# MCU.net
KiCad netlist of a schematic drawn in Altium Designer
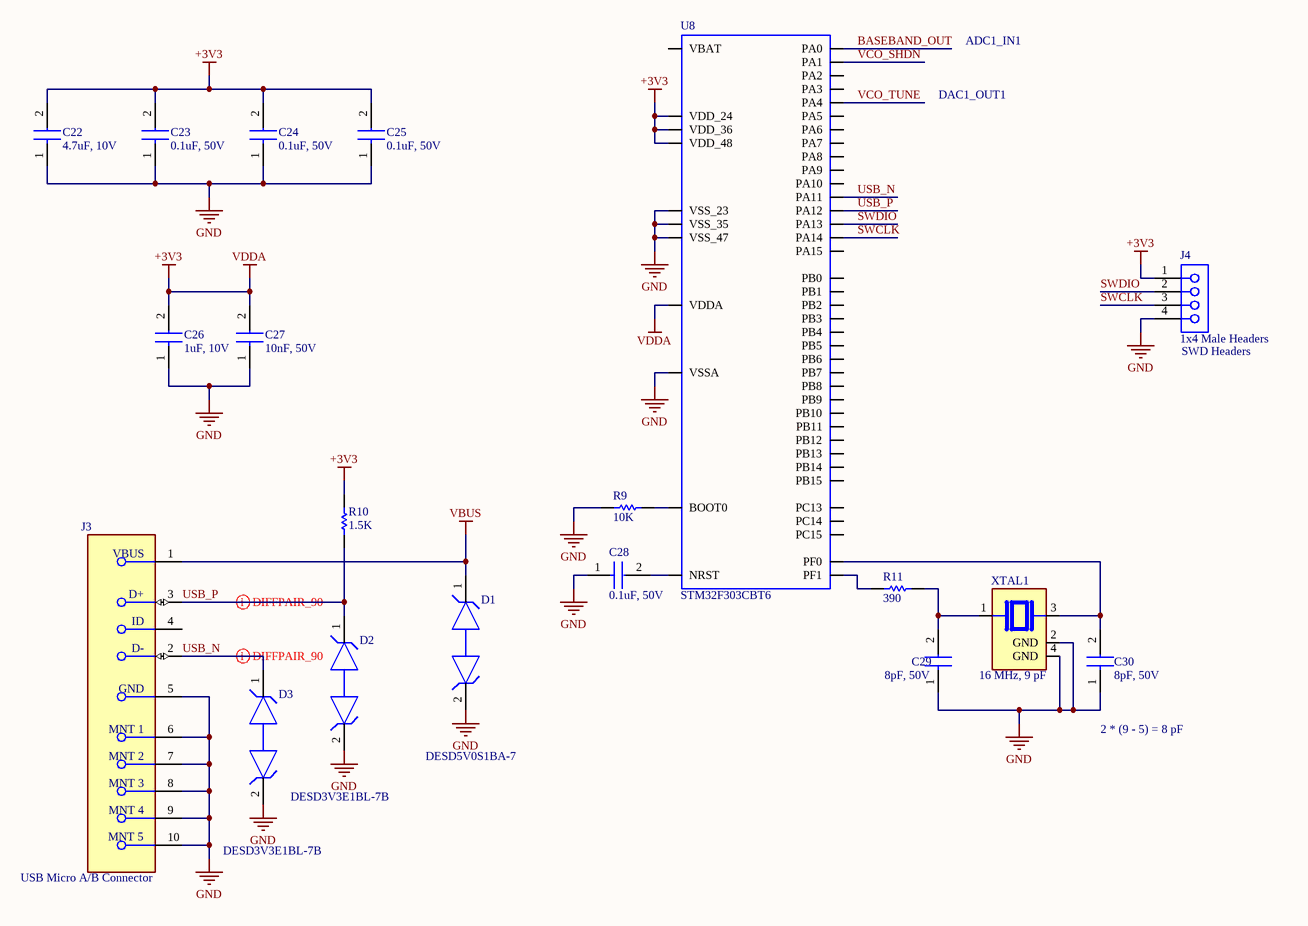
[diagram p0: MCU.SchDoc]

(export (version "E")
  (design (tool "Eeschema 10.0.6"))
  (components
    (comp (ref "C22")
      (value "4.7uF, 10V")
      (footprint "CAPC1608X90N")
      (fields
        (field (name "MANUFACTURER") "Samsung")
        (field (name "MANUFACTURER PART NUMBER") "CL10A475KP8NNNC")
      )
      (libsource (lib "FMCW-Radar-v1") (part "CL10A475KP8NNNC"))
    )
    (comp (ref "C23")
      (value "0.1uF, 50V")
      (footprint "CAP_CC0603_YAG-M")
      (fields
        (field (name "MANUFACTURER") "Yageo")
        (field (name "MANUFACTURER PART NUMBER") "CC0603JRX7R9BB104")
      )
      (libsource (lib "FMCW-Radar-v1") (part "CC0603JRX7R9BB104"))
    )
    (comp (ref "C24")
      (value "0.1uF, 50V")
      (footprint "CAP_CC0603_YAG-M")
      (fields
        (field (name "MANUFACTURER") "Yageo")
        (field (name "MANUFACTURER PART NUMBER") "CC0603JRX7R9BB104")
      )
      (libsource (lib "FMCW-Radar-v1") (part "CC0603JRX7R9BB104"))
    )
    (comp (ref "C25")
      (value "0.1uF, 50V")
      (footprint "CAP_CC0603_YAG-M")
      (fields
        (field (name "MANUFACTURER") "Yageo")
        (field (name "MANUFACTURER PART NUMBER") "CC0603JRX7R9BB104")
      )
      (libsource (lib "FMCW-Radar-v1") (part "CC0603JRX7R9BB104"))
    )
    (comp (ref "C26")
      (value "1uF, 10V")
      (footprint "FP-CL10-IPC_A")
      (fields
        (field (name "MANUFACTURER") "Samsung")
        (field (name "MANUFACTURER PART NUMBER") "CL10B105KP8NNNC")
      )
      (libsource (lib "FMCW-Radar-v1") (part "CL10B105KP8NNNC"))
    )
    (comp (ref "C27")
      (value "10nF, 50V")
      (footprint "CAPC10555_55N_KEM")
      (fields
        (field (name "MANUFACTURER") "KEMET")
        (field (name "MANUFACTURER PART NUMBER") "C0402C103K5RACTU")
      )
      (libsource (lib "FMCW-Radar-v1") (part "C0402C103K5RACTU"))
    )
    (comp (ref "C28")
      (value "0.1uF, 50V")
      (footprint "CAP_CC0603_YAG-M")
      (fields
        (field (name "MANUFACTURER") "Yageo")
        (field (name "MANUFACTURER PART NUMBER") "CC0603JRX7R9BB104")
      )
      (libsource (lib "FMCW-Radar-v1") (part "CC0603JRX7R9BB104"))
    )
    (comp (ref "C29")
      (value "8pF, 50V")
      (footprint "CAPC1005X55N")
      (fields
        (field (name "MANUFACTURER") "Murata")
        (field (name "MANUFACTURER PART NUMBER") "GJM1555C1H8R0BB01D")
      )
      (libsource (lib "FMCW-Radar-v1") (part "GJM1555C1H8R0BB01D"))
    )
    (comp (ref "C30")
      (value "8pF, 50V")
      (footprint "CAPC1005X55N")
      (fields
        (field (name "MANUFACTURER") "Murata")
        (field (name "MANUFACTURER PART NUMBER") "GJM1555C1H8R0BB01D")
      )
      (libsource (lib "FMCW-Radar-v1") (part "GJM1555C1H8R0BB01D"))
    )
    (comp (ref "D1")
      (value "DESD5V0S1BA-7")
      (footprint "FP-SOD323-IPC_C")
      (description "Trans Voltage Suppressor Diode, 130W, 5V V(RWM), Bidirectional, 2 Element, Silicon")
      (fields (field (name "MANUFACTURER") "Diodes Zetex"))
      (libsource (lib "FMCW-Radar-v1") (part "DESD5V0S1BA-7"))
    )
    (comp (ref "D2")
      (value "DESD3V3E1BL-7B")
      (footprint "CR_X1-DFN1006-2_DIO")
      (description "Trans Voltage Suppressor Diode, 35W, 3.3V V(RWM), Bidirectional, 1 Element, Silicon")
      (fields (field (name "MANUFACTURER") "Diodes"))
      (libsource (lib "FMCW-Radar-v1") (part "DESD3V3E1BL-7B"))
    )
    (comp (ref "D3")
      (value "DESD3V3E1BL-7B")
      (footprint "CR_X1-DFN1006-2_DIO")
      (description "Trans Voltage Suppressor Diode, 35W, 3.3V V(RWM), Bidirectional, 1 Element, Silicon")
      (fields (field (name "MANUFACTURER") "Diodes"))
      (libsource (lib "FMCW-Radar-v1") (part "DESD3V3E1BL-7B"))
    )
    (comp (ref "J3")
      (value "USB Micro A/B Connector")
      (footprint "FP-47590-0001-MFG")
      (description "USB Connector, 5 Contact(s), Female, Right Angle, Surface Mount Terminal, Locking, Receptacle")
      (fields (field (name "MANUFACTURER") "Molex") (field (name "MANUFACTURER PART NUMBER") "47590-0001"))
      (libsource (lib "FMCW-Radar-v1") (part "47590-0001"))
    )
    (comp (ref "J4")
      (value "1x4 Male Headers")
      (footprint "61300411121")
      (fields
        (field (name "MANUFACTURER") "Wurth Electronics")
        (field (name "MANUFACTURER PART NUMBER") "61300411121")
      )
      (libsource (lib "FMCW-Radar-v1") (part "61300411121"))
    )
    (comp (ref "R9")
      (value "10K")
      (footprint "RESC1005X37N")
      (fields
        (field (name "MANUFACTURER") "Yageo")
        (field (name "MANUFACTURER PART NUMBER") "AC0402FR-0710KL")
        (field (name "TOLERANCE") "1%")
      )
      (libsource (lib "FMCW-Radar-v1") (part "AC0402FR-0710KL"))
    )
    (comp (ref "R10")
      (value "1.5K")
      (footprint "RESC1005X40N")
      (fields
        (field (name "MANUFACTURER") "Yageo")
        (field (name "MANUFACTURER PART NUMBER") "RC0402FR-071K5L")
        (field (name "TOLERANCE") "1%")
      )
      (libsource (lib "FMCW-Radar-v1") (part "RC0402FR-071K5L"))
    )
    (comp (ref "R11")
      (value "390")
      (footprint "RESC1005X40N")
      (fields
        (field (name "MANUFACTURER") "Yageo")
        (field (name "MANUFACTURER PART NUMBER") "RC0402JR-07390RL")
        (field (name "TOLERANCE") "5%")
      )
      (libsource (lib "FMCW-Radar-v1") (part "RC0402JR-07390RL"))
    )
    (comp (ref "U8")
      (value "STM32F303CBT6")
      (footprint "LQFP-48")
      (description "RISC Microcontroller, 32-Bit, FLASH, CORTEX-M4F CPU, 72MHz, CMOS, PQFP48")
      (fields (field (name "MANUFACTURER") "STMicroelectronics"))
      (libsource (lib "FMCW-Radar-v1") (part "STM32F303CBT6"))
    )
    (comp (ref "XTAL1")
      (value "16 MHz, 9 pF")
      (footprint "XTAL_TSX-3225_16.0000MF18X-AC0")
      (description "Parallel - Fundamental Quartz Crystal, 16MHz Nom")
      (fields
        (field (name "MANUFACTURER") "Epson")
        (field (name "MANUFACTURER PART NUMBER") "TSX-3225 16.0000MF18X-AC0")
      )
      (libsource (lib "FMCW-Radar-v1") (part "TSX-3225 16.0000MF18X-AC0"))
    )
  )
  (nets
    (net (code "1") (name "+3V3") (class "Default")
      (node (ref "C22") (pin "2") (pinfunction "2_2") (pintype "passive"))
      (node (ref "C23") (pin "2") (pinfunction "2_2") (pintype "passive"))
      (node (ref "C24") (pin "2") (pinfunction "2_2") (pintype "passive"))
      (node (ref "C25") (pin "2") (pinfunction "2_2") (pintype "passive"))
      (node (ref "C26") (pin "2") (pinfunction "2_2") (pintype "passive"))
      (node (ref "C27") (pin "2") (pinfunction "2_2") (pintype "passive"))
      (node (ref "J4") (pin "1") (pinfunction "1_1") (pintype "passive"))
      (node (ref "R10") (pin "1") (pinfunction "1_1") (pintype "passive"))
      (node (ref "U8") (pin "24") (pinfunction "VDD_24_24") (pintype "bidirectional"))
      (node (ref "U8") (pin "36") (pinfunction "VDD_36_36") (pintype "bidirectional"))
      (node (ref "U8") (pin "48") (pinfunction "VDD_48_48") (pintype "bidirectional"))
      (node (ref "U8") (pin "9") (pinfunction "VDDA_9") (pintype "bidirectional"))
    )
    (net (code "2") (name "/BASEBAND_OUT") (class "Default")
      (node (ref "U8") (pin "10") (pinfunction "PA0_10") (pintype "bidirectional"))
    )
    (net (code "3") (name "/SWCLK") (class "Default")
      (node (ref "J4") (pin "3") (pinfunction "3_3") (pintype "passive"))
      (node (ref "U8") (pin "37") (pinfunction "PA14_37") (pintype "bidirectional"))
    )
    (net (code "4") (name "/SWDIO") (class "Default")
      (node (ref "J4") (pin "2") (pinfunction "2_2") (pintype "passive"))
      (node (ref "U8") (pin "34") (pinfunction "PA13_34") (pintype "bidirectional"))
    )
    (net (code "5") (name "/USB_N") (class "Default")
      (node (ref "D3") (pin "1") (pinfunction "1_1") (pintype "passive"))
      (node (ref "J3") (pin "2") (pinfunction "D-_2") (pintype "bidirectional"))
      (node (ref "U8") (pin "32") (pinfunction "PA11_32") (pintype "bidirectional"))
    )
    (net (code "6") (name "/USB_P") (class "Default")
      (node (ref "D2") (pin "1") (pinfunction "1_1") (pintype "passive"))
      (node (ref "J3") (pin "3") (pinfunction "D+_3") (pintype "bidirectional"))
      (node (ref "R10") (pin "2") (pinfunction "2_2") (pintype "passive"))
      (node (ref "U8") (pin "33") (pinfunction "PA12_33") (pintype "bidirectional"))
    )
    (net (code "7") (name "/VCO_SHDN") (class "Default")
      (node (ref "U8") (pin "11") (pinfunction "PA1_11") (pintype "bidirectional"))
    )
    (net (code "8") (name "/VCO_TUNE") (class "Default")
      (node (ref "U8") (pin "14") (pinfunction "PA4_14") (pintype "passive"))
    )
    (net (code "9") (name "GND") (class "Default")
      (node (ref "C22") (pin "1") (pinfunction "1_1") (pintype "passive"))
      (node (ref "C23") (pin "1") (pinfunction "1_1") (pintype "passive"))
      (node (ref "C24") (pin "1") (pinfunction "1_1") (pintype "passive"))
      (node (ref "C25") (pin "1") (pinfunction "1_1") (pintype "passive"))
      (node (ref "C26") (pin "1") (pinfunction "1_1") (pintype "passive"))
      (node (ref "C27") (pin "1") (pinfunction "1_1") (pintype "passive"))
      (node (ref "C28") (pin "1") (pinfunction "1_1") (pintype "passive"))
      (node (ref "C29") (pin "1") (pinfunction "1_1") (pintype "passive"))
      (node (ref "C30") (pin "1") (pinfunction "1_1") (pintype "passive"))
      (node (ref "D1") (pin "2") (pinfunction "2_2") (pintype "passive"))
      (node (ref "D2") (pin "2") (pinfunction "2_2") (pintype "passive"))
      (node (ref "D3") (pin "2") (pinfunction "2_2") (pintype "passive"))
      (node (ref "J3") (pin "10") (pinfunction "MNT_5_10") (pintype "passive"))
      (node (ref "J3") (pin "5") (pinfunction "GND_5") (pintype "power_in"))
      (node (ref "J3") (pin "6") (pinfunction "MNT_1_6") (pintype "passive"))
      (node (ref "J3") (pin "7") (pinfunction "MNT_2_7") (pintype "passive"))
      (node (ref "J3") (pin "8") (pinfunction "MNT_3_8") (pintype "passive"))
      (node (ref "J3") (pin "9") (pinfunction "MNT_4_9") (pintype "passive"))
      (node (ref "J4") (pin "4") (pinfunction "4_4") (pintype "passive"))
      (node (ref "R9") (pin "1") (pinfunction "1_1") (pintype "passive"))
      (node (ref "U8") (pin "23") (pinfunction "VSS_23_23") (pintype "bidirectional"))
      (node (ref "U8") (pin "35") (pinfunction "VSS_35_35") (pintype "bidirectional"))
      (node (ref "U8") (pin "47") (pinfunction "VSS_47_47") (pintype "bidirectional"))
      (node (ref "U8") (pin "8") (pinfunction "VSSA_8") (pintype "bidirectional"))
      (node (ref "XTAL1") (pin "2") (pinfunction "GND_2") (pintype "power_in"))
      (node (ref "XTAL1") (pin "4") (pinfunction "GND_4") (pintype "power_in"))
    )
    (net (code "10") (name "Net-(C29-Pad2)") (class "Default")
      (node (ref "C29") (pin "2") (pinfunction "2_2") (pintype "passive"))
      (node (ref "R11") (pin "2") (pinfunction "2_2") (pintype "passive"))
      (node (ref "XTAL1") (pin "1") (pinfunction "1_1") (pintype "passive"))
    )
    (net (code "11") (name "Net-(U8-BOOT0)") (class "Default")
      (node (ref "R9") (pin "2") (pinfunction "2_2") (pintype "passive"))
      (node (ref "U8") (pin "44") (pinfunction "BOOT0_44") (pintype "bidirectional"))
    )
    (net (code "12") (name "Net-(U8-NRST)") (class "Default")
      (node (ref "C28") (pin "2") (pinfunction "2_2") (pintype "passive"))
      (node (ref "U8") (pin "7") (pinfunction "NRST_7") (pintype "bidirectional"))
    )
    (net (code "13") (name "Net-(U8-PF0)") (class "Default")
      (node (ref "C30") (pin "2") (pinfunction "2_2") (pintype "passive"))
      (node (ref "U8") (pin "5") (pinfunction "PF0_5") (pintype "bidirectional"))
      (node (ref "XTAL1") (pin "3") (pinfunction "2_3") (pintype "passive"))
    )
    (net (code "14") (name "Net-(U8-PF1)") (class "Default")
      (node (ref "R11") (pin "1") (pinfunction "1_1") (pintype "passive"))
      (node (ref "U8") (pin "6") (pinfunction "PF1_6") (pintype "bidirectional"))
    )
    (net (code "15") (name "VBUS") (class "Default")
      (node (ref "D1") (pin "1") (pinfunction "1_1") (pintype "passive"))
      (node (ref "J3") (pin "1") (pinfunction "VBUS_1") (pintype "power_in"))
    )
    (net (code "16") (name "unconnected-(J3-ID-Pad4)") (class "Default")
      (node (ref "J3") (pin "4") (pinfunction "ID_4") (pintype "passive"))
    )
    (net (code "17") (name "unconnected-(U8-PA2-Pad12)") (class "Default")
      (node (ref "U8") (pin "12") (pinfunction "PA2_12") (pintype "bidirectional"))
    )
    (net (code "18") (name "unconnected-(U8-PA3-Pad13)") (class "Default")
      (node (ref "U8") (pin "13") (pinfunction "PA3_13") (pintype "bidirectional"))
    )
    (net (code "19") (name "unconnected-(U8-PA5-Pad15)") (class "Default")
      (node (ref "U8") (pin "15") (pinfunction "PA5_15") (pintype "bidirectional"))
    )
    (net (code "20") (name "unconnected-(U8-PA6-Pad16)") (class "Default")
      (node (ref "U8") (pin "16") (pinfunction "PA6_16") (pintype "bidirectional"))
    )
    (net (code "21") (name "unconnected-(U8-PA7-Pad17)") (class "Default")
      (node (ref "U8") (pin "17") (pinfunction "PA7_17") (pintype "bidirectional"))
    )
    (net (code "22") (name "unconnected-(U8-PA8-Pad29)") (class "Default")
      (node (ref "U8") (pin "29") (pinfunction "PA8_29") (pintype "bidirectional"))
    )
    (net (code "23") (name "unconnected-(U8-PA9-Pad30)") (class "Default")
      (node (ref "U8") (pin "30") (pinfunction "PA9_30") (pintype "bidirectional"))
    )
    (net (code "24") (name "unconnected-(U8-PA10-Pad31)") (class "Default")
      (node (ref "U8") (pin "31") (pinfunction "PA10_31") (pintype "bidirectional"))
    )
    (net (code "25") (name "unconnected-(U8-PA15-Pad38)") (class "Default")
      (node (ref "U8") (pin "38") (pinfunction "PA15_38") (pintype "bidirectional"))
    )
    (net (code "26") (name "unconnected-(U8-PB0-Pad18)") (class "Default")
      (node (ref "U8") (pin "18") (pinfunction "PB0_18") (pintype "bidirectional"))
    )
    (net (code "27") (name "unconnected-(U8-PB1-Pad19)") (class "Default")
      (node (ref "U8") (pin "19") (pinfunction "PB1_19") (pintype "bidirectional"))
    )
    (net (code "28") (name "unconnected-(U8-PB2-Pad20)") (class "Default")
      (node (ref "U8") (pin "20") (pinfunction "PB2_20") (pintype "bidirectional"))
    )
    (net (code "29") (name "unconnected-(U8-PB3-Pad39)") (class "Default")
      (node (ref "U8") (pin "39") (pinfunction "PB3_39") (pintype "bidirectional"))
    )
    (net (code "30") (name "unconnected-(U8-PB4-Pad40)") (class "Default")
      (node (ref "U8") (pin "40") (pinfunction "PB4_40") (pintype "bidirectional"))
    )
    (net (code "31") (name "unconnected-(U8-PB5-Pad41)") (class "Default")
      (node (ref "U8") (pin "41") (pinfunction "PB5_41") (pintype "bidirectional"))
    )
    (net (code "32") (name "unconnected-(U8-PB6-Pad42)") (class "Default")
      (node (ref "U8") (pin "42") (pinfunction "PB6_42") (pintype "bidirectional"))
    )
    (net (code "33") (name "unconnected-(U8-PB7-Pad43)") (class "Default")
      (node (ref "U8") (pin "43") (pinfunction "PB7_43") (pintype "bidirectional"))
    )
    (net (code "34") (name "unconnected-(U8-PB8-Pad45)") (class "Default")
      (node (ref "U8") (pin "45") (pinfunction "PB8_45") (pintype "bidirectional"))
    )
    (net (code "35") (name "unconnected-(U8-PB9-Pad46)") (class "Default")
      (node (ref "U8") (pin "46") (pinfunction "PB9_46") (pintype "bidirectional"))
    )
    (net (code "36") (name "unconnected-(U8-PB10-Pad21)") (class "Default")
      (node (ref "U8") (pin "21") (pinfunction "PB10_21") (pintype "bidirectional"))
    )
    (net (code "37") (name "unconnected-(U8-PB11-Pad22)") (class "Default")
      (node (ref "U8") (pin "22") (pinfunction "PB11_22") (pintype "bidirectional"))
    )
    (net (code "38") (name "unconnected-(U8-PB12-Pad25)") (class "Default")
      (node (ref "U8") (pin "25") (pinfunction "PB12_25") (pintype "bidirectional"))
    )
    (net (code "39") (name "unconnected-(U8-PB13-Pad26)") (class "Default")
      (node (ref "U8") (pin "26") (pinfunction "PB13_26") (pintype "bidirectional"))
    )
    (net (code "40") (name "unconnected-(U8-PB14-Pad27)") (class "Default")
      (node (ref "U8") (pin "27") (pinfunction "PB14_27") (pintype "bidirectional"))
    )
    (net (code "41") (name "unconnected-(U8-PB15-Pad28)") (class "Default")
      (node (ref "U8") (pin "28") (pinfunction "PB15_28") (pintype "bidirectional"))
    )
    (net (code "42") (name "unconnected-(U8-PC13-Pad2)") (class "Default")
      (node (ref "U8") (pin "2") (pinfunction "PC13_2") (pintype "bidirectional"))
    )
    (net (code "43") (name "unconnected-(U8-PC14-Pad3)") (class "Default")
      (node (ref "U8") (pin "3") (pinfunction "PC14_3") (pintype "bidirectional"))
    )
    (net (code "44") (name "unconnected-(U8-PC15-Pad4)") (class "Default")
      (node (ref "U8") (pin "4") (pinfunction "PC15_4") (pintype "bidirectional"))
    )
    (net (code "45") (name "unconnected-(U8-VBAT-Pad1)") (class "Default")
      (node (ref "U8") (pin "1") (pinfunction "VBAT_1") (pintype "bidirectional"))
    )
  )
)
